# ospi_v10.net
KiCad netlist of a schematic drawn in EAGLE
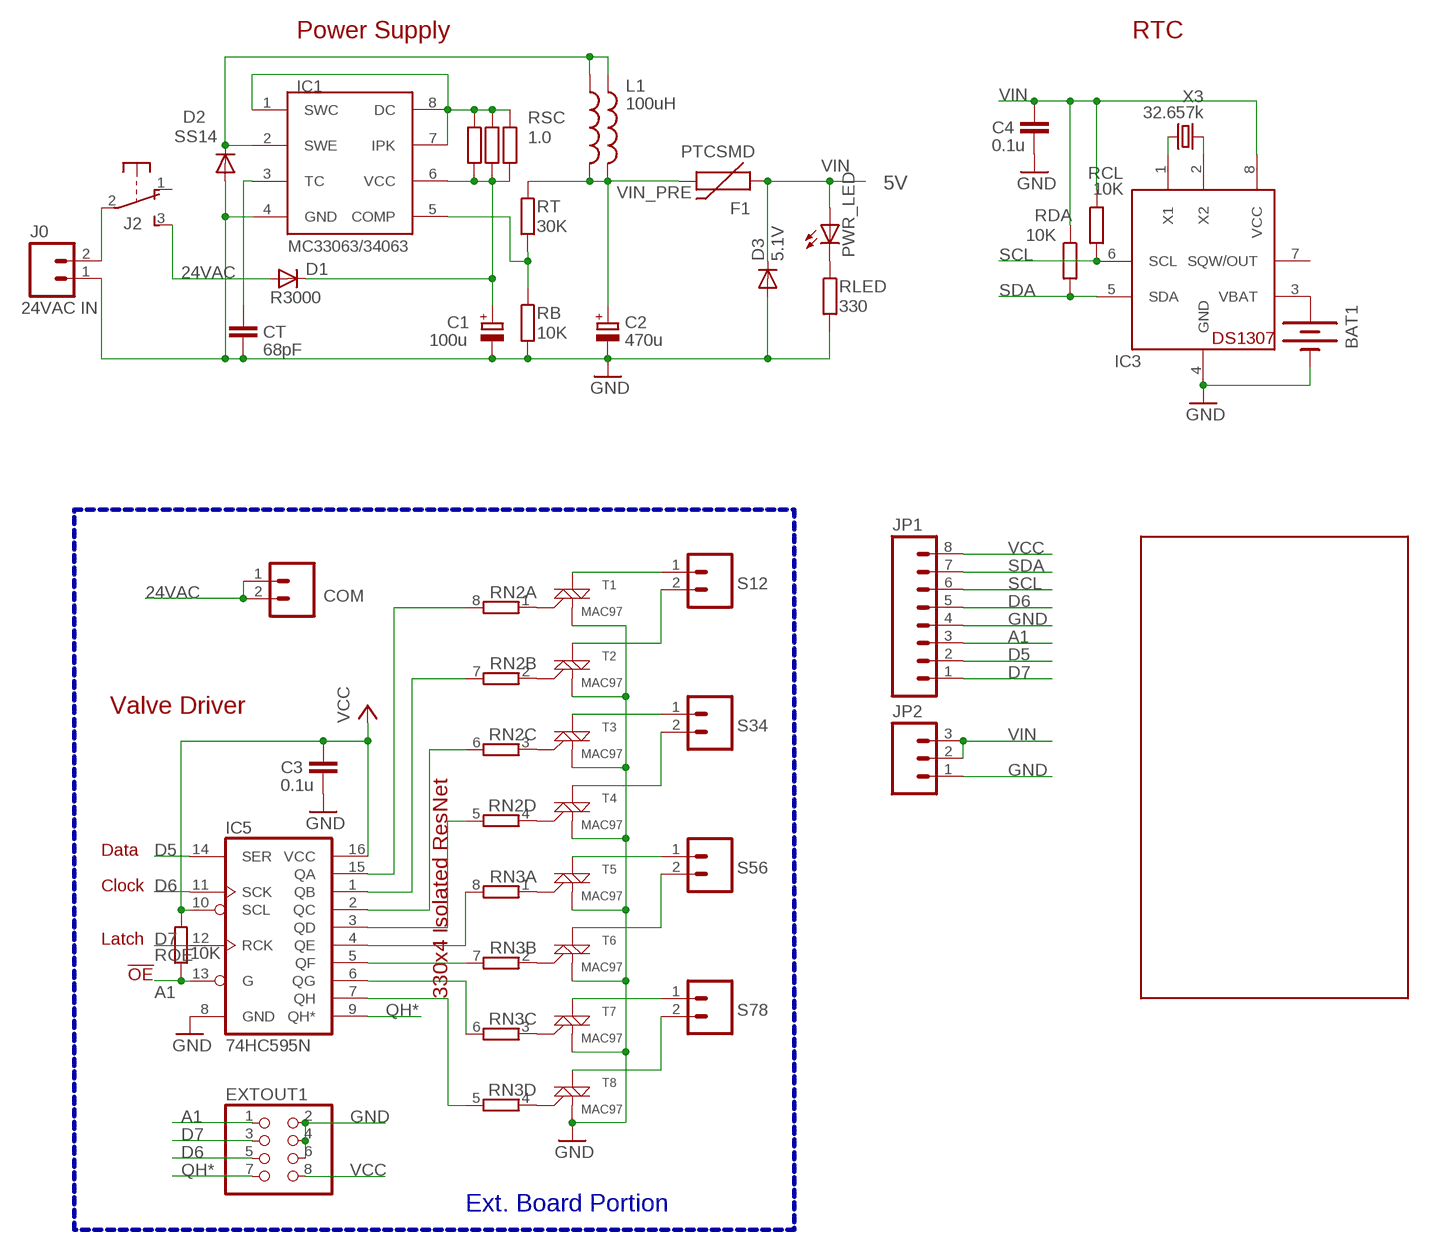
[diagram p0: schematic, sheet 1]

(export (version "E")
  (design (tool "Eeschema 10.0.6"))
  (components
    (comp (ref "BAT1")
      (value "BATTERYBATTERY_12MM_SMT")
      (footprint "eagle-import:BATTCON_12MM_SMT")
      (libsource (lib "eagle-import") (part "BATTERYBATTERY_12MM_SMT"))
    )
    (comp (ref "C1")
      (value "100u")
      (footprint "eagle-import:E3,5-8")
      (libsource (lib "eagle-import") (part "CPOL-EUE3.5-8"))
    )
    (comp (ref "C2")
      (value "470u")
      (footprint "eagle-import:E3,5-8")
      (libsource (lib "eagle-import") (part "CPOL-EUE3.5-8"))
    )
    (comp (ref "C3")
      (value "0.1u")
      (footprint "eagle-import:C0805")
      (libsource (lib "eagle-import") (part "C-EUC0805"))
    )
    (comp (ref "C4")
      (value "0.1u")
      (footprint "eagle-import:C0805")
      (libsource (lib "eagle-import") (part "C-EUC0805"))
    )
    (comp (ref "COM")
      (value "M025MM")
      (footprint "eagle-import:SCREWTERMINAL-5MM-2")
      (libsource (lib "eagle-import") (part "M025MM"))
    )
    (comp (ref "CT")
      (value "68pF")
      (footprint "eagle-import:C0805")
      (libsource (lib "eagle-import") (part "C-EUC0805"))
    )
    (comp (ref "D1")
      (value "R3000")
      (footprint "eagle-import:DO41-7.6")
      (libsource (lib "eagle-import") (part "DIODE-DO41-7.6"))
    )
    (comp (ref "D2")
      (value "SS14")
      (footprint "eagle-import:DO-214AC")
      (libsource (lib "eagle-import") (part "DIODE-DO-214AC"))
    )
    (comp (ref "D3")
      (value "5.1V")
      (footprint "eagle-import:DO34-7")
      (libsource (lib "eagle-import") (part "DIODE-DO34-7"))
    )
    (comp (ref "EXTOUT1")
      (value "PINHD-2X4/90")
      (footprint "eagle-import:2X04_90")
      (libsource (lib "eagle-import") (part "PINHD-2X4/90"))
    )
    (comp (ref "F1")
      (value "PTCSMD")
      (footprint "eagle-import:PTC-1206")
      (libsource (lib "eagle-import") (part "PTCSMD"))
    )
    (comp (ref "IC1")
      (value "MC33063/MC34063D")
      (footprint "eagle-import:SO08")
      (libsource (lib "eagle-import") (part "MC33063/MC34063D"))
    )
    (comp (ref "IC3")
      (value "DS1307")
      (footprint "eagle-import:SO08")
      (libsource (lib "eagle-import") (part "DS1307SOIC"))
    )
    (comp (ref "IC5")
      (value "74HC595N")
      (footprint "eagle-import:SO16")
      (libsource (lib "eagle-import") (part "74595DLS"))
    )
    (comp (ref "J0")
      (value "24VAC IN")
      (footprint "eagle-import:SCREWTERMINAL-5MM-2")
      (libsource (lib "eagle-import") (part "M025MM"))
    )
    (comp (ref "J2")
      (value "EG1206")
      (footprint "eagle-import:EG1206")
      (libsource (lib "eagle-import") (part "EG1206"))
    )
    (comp (ref "JP1")
      (value "M08LOCK")
      (footprint "eagle-import:1X08_LOCK")
      (libsource (lib "eagle-import") (part "M08LOCK"))
    )
    (comp (ref "JP2")
      (value "M03LOCK")
      (footprint "eagle-import:1X03_LOCK")
      (libsource (lib "eagle-import") (part "M03LOCK"))
    )
    (comp (ref "L1")
      (value "100uH")
      (footprint "eagle-import:SRU1038")
      (libsource (lib "eagle-import") (part "INDUCTORSRU1038"))
    )
    (comp (ref "L1'")
      (value "220uH")
      (footprint "eagle-import:6000-XXXX-RC")
      (libsource (lib "eagle-import") (part "L-US6000-XXX-RC"))
    )
    (comp (ref "PWR_LED")
      (value "LEDCHIPLED_0805")
      (footprint "eagle-import:CHIPLED_0805")
      (libsource (lib "eagle-import") (part "LEDCHIPLED_0805"))
    )
    (comp (ref "RB")
      (value "10K")
      (footprint "eagle-import:R0805")
      (libsource (lib "eagle-import") (part "R-EU_R0805"))
    )
    (comp (ref "RCL")
      (value "10K")
      (footprint "eagle-import:R0805")
      (libsource (lib "eagle-import") (part "R-EU_R0805"))
    )
    (comp (ref "RDA")
      (value "10K")
      (footprint "eagle-import:R0805")
      (libsource (lib "eagle-import") (part "R-EU_R0805"))
    )
    (comp (ref "RLED")
      (value "330")
      (footprint "eagle-import:R0805")
      (libsource (lib "eagle-import") (part "R-EU_R0805"))
    )
    (comp (ref "RN2")
      (value "4R-NEXB38V")
      (footprint "eagle-import:EXB38V")
      (libsource (lib "eagle-import") (part "4R-NEXB38V"))
    )
    (comp (ref "RN3")
      (value "4R-NEXB38V")
      (footprint "eagle-import:EXB38V")
      (libsource (lib "eagle-import") (part "4R-NEXB38V"))
    )
    (comp (ref "ROE")
      (value "10K")
      (footprint "eagle-import:R0805")
      (libsource (lib "eagle-import") (part "R-EU_R0805"))
    )
    (comp (ref "RSC")
      (value "1.0")
      (footprint "eagle-import:R0805")
      (libsource (lib "eagle-import") (part "R-EU_R0805"))
    )
    (comp (ref "RSC1")
      (value "1.0")
      (footprint "eagle-import:R0805")
      (libsource (lib "eagle-import") (part "R-EU_R0805"))
    )
    (comp (ref "RSC2")
      (value "1.0")
      (footprint "eagle-import:R0805")
      (libsource (lib "eagle-import") (part "R-EU_R0805"))
    )
    (comp (ref "RT")
      (value "30K")
      (footprint "eagle-import:R0805")
      (libsource (lib "eagle-import") (part "R-EU_R0805"))
    )
    (comp (ref "S12")
      (value "M025MM")
      (footprint "eagle-import:SCREWTERMINAL-5MM-2")
      (libsource (lib "eagle-import") (part "M025MM"))
    )
    (comp (ref "S34")
      (value "M025MM")
      (footprint "eagle-import:SCREWTERMINAL-5MM-2")
      (libsource (lib "eagle-import") (part "M025MM"))
    )
    (comp (ref "S56")
      (value "M025MM")
      (footprint "eagle-import:SCREWTERMINAL-5MM-2")
      (libsource (lib "eagle-import") (part "M025MM"))
    )
    (comp (ref "S78")
      (value "M025MM")
      (footprint "eagle-import:SCREWTERMINAL-5MM-2")
      (libsource (lib "eagle-import") (part "M025MM"))
    )
    (comp (ref "T1")
      (value "MAC97")
      (footprint "eagle-import:SOT223")
      (libsource (lib "eagle-import") (part "MAC97SOT223"))
    )
    (comp (ref "T2")
      (value "MAC97")
      (footprint "eagle-import:SOT223")
      (libsource (lib "eagle-import") (part "MAC97SOT223"))
    )
    (comp (ref "T3")
      (value "MAC97")
      (footprint "eagle-import:SOT223")
      (libsource (lib "eagle-import") (part "MAC97SOT223"))
    )
    (comp (ref "T4")
      (value "MAC97")
      (footprint "eagle-import:SOT223")
      (libsource (lib "eagle-import") (part "MAC97SOT223"))
    )
    (comp (ref "T5")
      (value "MAC97")
      (footprint "eagle-import:SOT223")
      (libsource (lib "eagle-import") (part "MAC97SOT223"))
    )
    (comp (ref "T6")
      (value "MAC97")
      (footprint "eagle-import:SOT223")
      (libsource (lib "eagle-import") (part "MAC97SOT223"))
    )
    (comp (ref "T7")
      (value "MAC97")
      (footprint "eagle-import:SOT223")
      (libsource (lib "eagle-import") (part "MAC97SOT223"))
    )
    (comp (ref "T8")
      (value "MAC97")
      (footprint "eagle-import:SOT223")
      (libsource (lib "eagle-import") (part "MAC97SOT223"))
    )
    (comp (ref "U$2")
      (value "OSPI")
      (footprint "eagle-import:OSPI")
      (libsource (lib "eagle-import") (part "OSPI"))
    )
    (comp (ref "X3")
      (value "32.657k")
      (footprint "eagle-import:TC26H")
      (libsource (lib "eagle-import") (part "CRYSTALTC26H"))
    )
  )
  (nets
    (net (code "1") (name "/24VAC") (class "Default")
      (node (ref "COM") (pin "1") (pinfunction "1_1") (pintype "passive"))
      (node (ref "COM") (pin "2") (pinfunction "2_2") (pintype "passive"))
      (node (ref "D1") (pin "A") (pinfunction "A_A") (pintype "passive"))
      (node (ref "J2") (pin "3") (pinfunction "S_3") (pintype "passive"))
    )
    (net (code "2") (name "/A1") (class "Default")
      (node (ref "EXTOUT1") (pin "1") (pinfunction "1_1") (pintype "passive"))
      (node (ref "IC5") (pin "13") (pinfunction "G_13") (pintype "input"))
      (node (ref "JP1") (pin "3") (pinfunction "3_3") (pintype "passive"))
      (node (ref "ROE") (pin "1") (pinfunction "1_1") (pintype "passive"))
    )
    (net (code "3") (name "/D5") (class "Default")
      (node (ref "IC5") (pin "14") (pinfunction "SER_14") (pintype "input"))
      (node (ref "JP1") (pin "2") (pinfunction "2_2") (pintype "passive"))
    )
    (net (code "4") (name "/D6") (class "Default")
      (node (ref "EXTOUT1") (pin "5") (pinfunction "5_5") (pintype "passive"))
      (node (ref "IC5") (pin "11") (pinfunction "SCK_11") (pintype "input"))
      (node (ref "JP1") (pin "5") (pinfunction "5_5") (pintype "passive"))
    )
    (net (code "5") (name "/D7") (class "Default")
      (node (ref "EXTOUT1") (pin "3") (pinfunction "3_3") (pintype "passive"))
      (node (ref "IC5") (pin "12") (pinfunction "RCK_12") (pintype "input"))
      (node (ref "JP1") (pin "1") (pinfunction "1_1") (pintype "passive"))
    )
    (net (code "6") (name "/QH*") (class "Default")
      (node (ref "EXTOUT1") (pin "7") (pinfunction "7_7") (pintype "passive"))
      (node (ref "IC5") (pin "9") (pinfunction "QH*_9") (pintype "tri_state"))
    )
    (net (code "7") (name "/SCL") (class "Default")
      (node (ref "IC3") (pin "6") (pinfunction "SCL_6") (pintype "bidirectional"))
      (node (ref "JP1") (pin "6") (pinfunction "6_6") (pintype "passive"))
      (node (ref "RCL") (pin "2") (pinfunction "2_2") (pintype "passive"))
    )
    (net (code "8") (name "/SDA") (class "Default")
      (node (ref "IC3") (pin "5") (pinfunction "SDA_5") (pintype "bidirectional"))
      (node (ref "JP1") (pin "7") (pinfunction "7_7") (pintype "passive"))
      (node (ref "RDA") (pin "2") (pinfunction "2_2") (pintype "passive"))
    )
    (net (code "9") (name "/VIN") (class "Default")
      (node (ref "C4") (pin "1") (pinfunction "1_1") (pintype "passive"))
      (node (ref "D3") (pin "C") (pinfunction "C_C") (pintype "passive"))
      (node (ref "F1") (pin "1") (pinfunction "1_1") (pintype "bidirectional"))
      (node (ref "IC3") (pin "8") (pinfunction "VCC_8") (pintype "power_in"))
      (node (ref "JP2") (pin "2") (pinfunction "2_2") (pintype "passive"))
      (node (ref "JP2") (pin "3") (pinfunction "3_3") (pintype "passive"))
      (node (ref "PWR_LED") (pin "A") (pinfunction "A_A") (pintype "passive"))
      (node (ref "RCL") (pin "1") (pinfunction "1_1") (pintype "passive"))
      (node (ref "RDA") (pin "1") (pinfunction "1_1") (pintype "passive"))
    )
    (net (code "10") (name "/VIN_PRE") (class "Default")
      (node (ref "C2") (pin "+") (pinfunction "+_+") (pintype "passive"))
      (node (ref "F1") (pin "2") (pinfunction "2_2") (pintype "bidirectional"))
      (node (ref "L1") (pin "2") (pinfunction "2_2") (pintype "passive"))
      (node (ref "L1'") (pin "2") (pinfunction "2_2") (pintype "passive"))
      (node (ref "RT") (pin "1") (pinfunction "1_1") (pintype "passive"))
    )
    (net (code "11") (name "GND") (class "Default")
      (node (ref "BAT1") (pin "P$1") (pinfunction "-_P$1") (pintype "power_in"))
      (node (ref "C1") (pin "-") (pinfunction "-_-") (pintype "passive"))
      (node (ref "C2") (pin "-") (pinfunction "-_-") (pintype "passive"))
      (node (ref "C3") (pin "2") (pinfunction "2_2") (pintype "passive"))
      (node (ref "C4") (pin "2") (pinfunction "2_2") (pintype "passive"))
      (node (ref "CT") (pin "2") (pinfunction "2_2") (pintype "passive"))
      (node (ref "D2") (pin "A") (pinfunction "A_A") (pintype "passive"))
      (node (ref "D3") (pin "A") (pinfunction "A_A") (pintype "passive"))
      (node (ref "EXTOUT1") (pin "2") (pinfunction "2_2") (pintype "passive"))
      (node (ref "EXTOUT1") (pin "4") (pinfunction "4_4") (pintype "passive"))
      (node (ref "EXTOUT1") (pin "6") (pinfunction "6_6") (pintype "passive"))
      (node (ref "IC1") (pin "4") (pinfunction "GND_4") (pintype "power_in"))
      (node (ref "IC3") (pin "4") (pinfunction "GND_4") (pintype "power_in"))
      (node (ref "IC5") (pin "8") (pinfunction "GND_8") (pintype "power_in"))
      (node (ref "J0") (pin "1") (pinfunction "1_1") (pintype "passive"))
      (node (ref "JP1") (pin "4") (pinfunction "4_4") (pintype "passive"))
      (node (ref "JP2") (pin "1") (pinfunction "1_1") (pintype "passive"))
      (node (ref "RB") (pin "2") (pinfunction "2_2") (pintype "passive"))
      (node (ref "RLED") (pin "2") (pinfunction "2_2") (pintype "passive"))
      (node (ref "T1") (pin "1") (pinfunction "M1_1") (pintype "bidirectional"))
      (node (ref "T2") (pin "1") (pinfunction "M1_1") (pintype "bidirectional"))
      (node (ref "T3") (pin "1") (pinfunction "M1_1") (pintype "bidirectional"))
      (node (ref "T4") (pin "1") (pinfunction "M1_1") (pintype "bidirectional"))
      (node (ref "T5") (pin "1") (pinfunction "M1_1") (pintype "bidirectional"))
      (node (ref "T6") (pin "1") (pinfunction "M1_1") (pintype "bidirectional"))
      (node (ref "T7") (pin "1") (pinfunction "M1_1") (pintype "bidirectional"))
      (node (ref "T8") (pin "1") (pinfunction "M1_1") (pintype "bidirectional"))
    )
    (net (code "12") (name "Net-(BAT1-+)") (class "Default")
      (node (ref "BAT1") (pin "P$2") (pinfunction "+_P$2") (pintype "power_in"))
      (node (ref "IC3") (pin "3") (pinfunction "VBAT_3") (pintype "power_in"))
    )
    (net (code "13") (name "Net-(IC1-COMP)") (class "Default")
      (node (ref "IC1") (pin "5") (pinfunction "COMP_5") (pintype "input"))
      (node (ref "RB") (pin "1") (pinfunction "1_1") (pintype "passive"))
      (node (ref "RT") (pin "2") (pinfunction "2_2") (pintype "passive"))
    )
    (net (code "14") (name "Net-(IC1-DC)") (class "Default")
      (node (ref "IC1") (pin "1") (pinfunction "SWC_1") (pintype "input"))
      (node (ref "IC1") (pin "7") (pinfunction "IPK_7") (pintype "bidirectional"))
      (node (ref "IC1") (pin "8") (pinfunction "DC_8") (pintype "input"))
      (node (ref "RSC") (pin "1") (pinfunction "1_1") (pintype "passive"))
      (node (ref "RSC1") (pin "1") (pinfunction "1_1") (pintype "passive"))
      (node (ref "RSC2") (pin "1") (pinfunction "1_1") (pintype "passive"))
    )
    (net (code "15") (name "Net-(IC1-SWE)") (class "Default")
      (node (ref "D2") (pin "C") (pinfunction "C_C") (pintype "passive"))
      (node (ref "IC1") (pin "2") (pinfunction "SWE_2") (pintype "input"))
      (node (ref "L1") (pin "1") (pinfunction "1_1") (pintype "passive"))
      (node (ref "L1'") (pin "1") (pinfunction "1_1") (pintype "passive"))
    )
    (net (code "16") (name "Net-(IC1-TC)") (class "Default")
      (node (ref "CT") (pin "1") (pinfunction "1_1") (pintype "passive"))
      (node (ref "IC1") (pin "3") (pinfunction "TC_3") (pintype "input"))
    )
    (net (code "17") (name "Net-(IC1-VCC)") (class "Default")
      (node (ref "C1") (pin "+") (pinfunction "+_+") (pintype "passive"))
      (node (ref "D1") (pin "C") (pinfunction "C_C") (pintype "passive"))
      (node (ref "IC1") (pin "6") (pinfunction "VCC_6") (pintype "power_in"))
      (node (ref "RSC") (pin "2") (pinfunction "2_2") (pintype "passive"))
      (node (ref "RSC1") (pin "2") (pinfunction "2_2") (pintype "passive"))
      (node (ref "RSC2") (pin "2") (pinfunction "2_2") (pintype "passive"))
    )
    (net (code "18") (name "Net-(IC3-X1)") (class "Default")
      (node (ref "IC3") (pin "1") (pinfunction "X1_1") (pintype "passive"))
      (node (ref "X3") (pin "1") (pinfunction "1_1") (pintype "passive"))
    )
    (net (code "19") (name "Net-(IC3-X2)") (class "Default")
      (node (ref "IC3") (pin "2") (pinfunction "X2_2") (pintype "passive"))
      (node (ref "X3") (pin "2") (pinfunction "2_2") (pintype "passive"))
    )
    (net (code "20") (name "Net-(IC5-QA)") (class "Default")
      (node (ref "IC5") (pin "15") (pinfunction "QA_15") (pintype "tri_state"))
      (node (ref "RN2") (pin "8") (pinfunction "2_8") (pintype "passive"))
    )
    (net (code "21") (name "Net-(IC5-QB)") (class "Default")
      (node (ref "IC5") (pin "1") (pinfunction "QB_1") (pintype "tri_state"))
      (node (ref "RN2") (pin "7") (pinfunction "2_7") (pintype "passive"))
    )
    (net (code "22") (name "Net-(IC5-QC)") (class "Default")
      (node (ref "IC5") (pin "2") (pinfunction "QC_2") (pintype "tri_state"))
      (node (ref "RN2") (pin "6") (pinfunction "2_6") (pintype "passive"))
    )
    (net (code "23") (name "Net-(IC5-QD)") (class "Default")
      (node (ref "IC5") (pin "3") (pinfunction "QD_3") (pintype "tri_state"))
      (node (ref "RN2") (pin "5") (pinfunction "2_5") (pintype "passive"))
    )
    (net (code "24") (name "Net-(IC5-QE)") (class "Default")
      (node (ref "IC5") (pin "4") (pinfunction "QE_4") (pintype "tri_state"))
      (node (ref "RN3") (pin "8") (pinfunction "2_8") (pintype "passive"))
    )
    (net (code "25") (name "Net-(IC5-QF)") (class "Default")
      (node (ref "IC5") (pin "5") (pinfunction "QF_5") (pintype "tri_state"))
      (node (ref "RN3") (pin "7") (pinfunction "2_7") (pintype "passive"))
    )
    (net (code "26") (name "Net-(IC5-QG)") (class "Default")
      (node (ref "IC5") (pin "6") (pinfunction "QG_6") (pintype "tri_state"))
      (node (ref "RN3") (pin "6") (pinfunction "2_6") (pintype "passive"))
    )
    (net (code "27") (name "Net-(IC5-QH)") (class "Default")
      (node (ref "IC5") (pin "7") (pinfunction "QH_7") (pintype "tri_state"))
      (node (ref "RN3") (pin "5") (pinfunction "2_5") (pintype "passive"))
    )
    (net (code "28") (name "Net-(J2-P)") (class "Default")
      (node (ref "J0") (pin "2") (pinfunction "2_2") (pintype "passive"))
      (node (ref "J2") (pin "2") (pinfunction "P_2") (pintype "passive"))
    )
    (net (code "29") (name "Net-(PWR_LED-PadC)") (class "Default")
      (node (ref "PWR_LED") (pin "C") (pinfunction "C_C") (pintype "passive"))
      (node (ref "RLED") (pin "1") (pinfunction "1_1") (pintype "passive"))
    )
    (net (code "30") (name "Net-(RN2B-1)") (class "Default")
      (node (ref "RN2") (pin "2") (pinfunction "1_2") (pintype "passive"))
      (node (ref "T2") (pin "3") (pinfunction "G_3") (pintype "bidirectional"))
    )
    (net (code "31") (name "Net-(RN2C-1)") (class "Default")
      (node (ref "RN2") (pin "3") (pinfunction "1_3") (pintype "passive"))
      (node (ref "T3") (pin "3") (pinfunction "G_3") (pintype "bidirectional"))
    )
    (net (code "32") (name "Net-(RN2D-1)") (class "Default")
      (node (ref "RN2") (pin "4") (pinfunction "1_4") (pintype "passive"))
      (node (ref "T4") (pin "3") (pinfunction "G_3") (pintype "bidirectional"))
    )
    (net (code "33") (name "Net-(RN3B-1)") (class "Default")
      (node (ref "RN3") (pin "2") (pinfunction "1_2") (pintype "passive"))
      (node (ref "T6") (pin "3") (pinfunction "G_3") (pintype "bidirectional"))
    )
    (net (code "34") (name "Net-(RN3C-1)") (class "Default")
      (node (ref "RN3") (pin "3") (pinfunction "1_3") (pintype "passive"))
      (node (ref "T7") (pin "3") (pinfunction "G_3") (pintype "bidirectional"))
    )
    (net (code "35") (name "Net-(RN3D-1)") (class "Default")
      (node (ref "RN3") (pin "4") (pinfunction "1_4") (pintype "passive"))
      (node (ref "T8") (pin "3") (pinfunction "G_3") (pintype "bidirectional"))
    )
    (net (code "36") (name "Net-(T1-G)") (class "Default")
      (node (ref "RN2") (pin "1") (pinfunction "1_1") (pintype "passive"))
      (node (ref "T1") (pin "3") (pinfunction "G_3") (pintype "bidirectional"))
    )
    (net (code "37") (name "Net-(T1-M2)") (class "Default")
      (node (ref "S12") (pin "1") (pinfunction "1_1") (pintype "passive"))
      (node (ref "T1") (pin "4") (pinfunction "M2_4") (pintype "bidirectional"))
    )
    (net (code "38") (name "Net-(T2-M2)") (class "Default")
      (node (ref "S12") (pin "2") (pinfunction "2_2") (pintype "passive"))
      (node (ref "T2") (pin "4") (pinfunction "M2_4") (pintype "bidirectional"))
    )
    (net (code "39") (name "Net-(T3-M2)") (class "Default")
      (node (ref "S34") (pin "1") (pinfunction "1_1") (pintype "passive"))
      (node (ref "T3") (pin "4") (pinfunction "M2_4") (pintype "bidirectional"))
    )
    (net (code "40") (name "Net-(T4-M2)") (class "Default")
      (node (ref "S34") (pin "2") (pinfunction "2_2") (pintype "passive"))
      (node (ref "T4") (pin "4") (pinfunction "M2_4") (pintype "bidirectional"))
    )
    (net (code "41") (name "Net-(T5-G)") (class "Default")
      (node (ref "RN3") (pin "1") (pinfunction "1_1") (pintype "passive"))
      (node (ref "T5") (pin "3") (pinfunction "G_3") (pintype "bidirectional"))
    )
    (net (code "42") (name "Net-(T5-M2)") (class "Default")
      (node (ref "S56") (pin "1") (pinfunction "1_1") (pintype "passive"))
      (node (ref "T5") (pin "4") (pinfunction "M2_4") (pintype "bidirectional"))
    )
    (net (code "43") (name "Net-(T6-M2)") (class "Default")
      (node (ref "S56") (pin "2") (pinfunction "2_2") (pintype "passive"))
      (node (ref "T6") (pin "4") (pinfunction "M2_4") (pintype "bidirectional"))
    )
    (net (code "44") (name "Net-(T7-M2)") (class "Default")
      (node (ref "S78") (pin "1") (pinfunction "1_1") (pintype "passive"))
      (node (ref "T7") (pin "4") (pinfunction "M2_4") (pintype "bidirectional"))
    )
    (net (code "45") (name "Net-(T8-M2)") (class "Default")
      (node (ref "S78") (pin "2") (pinfunction "2_2") (pintype "passive"))
      (node (ref "T8") (pin "4") (pinfunction "M2_4") (pintype "bidirectional"))
    )
    (net (code "46") (name "VCC") (class "Default")
      (node (ref "C3") (pin "1") (pinfunction "1_1") (pintype "passive"))
      (node (ref "EXTOUT1") (pin "8") (pinfunction "8_8") (pintype "passive"))
      (node (ref "IC5") (pin "10") (pinfunction "SCL_10") (pintype "input"))
      (node (ref "IC5") (pin "16") (pinfunction "VCC_16") (pintype "power_in"))
      (node (ref "JP1") (pin "8") (pinfunction "8_8") (pintype "passive"))
      (node (ref "ROE") (pin "2") (pinfunction "2_2") (pintype "passive"))
    )
    (net (code "47") (name "unconnected-(IC3-SQW{slash}OUT-Pad7)") (class "Default")
      (node (ref "IC3") (pin "7") (pinfunction "SQW/OUT_7") (pintype "bidirectional"))
    )
    (net (code "48") (name "unconnected-(J2-O-Pad1)") (class "Default")
      (node (ref "J2") (pin "1") (pinfunction "O_1") (pintype "passive"))
    )
  )
)
